# Sheet3.net
KiCad netlist of a schematic drawn in Altium Designer
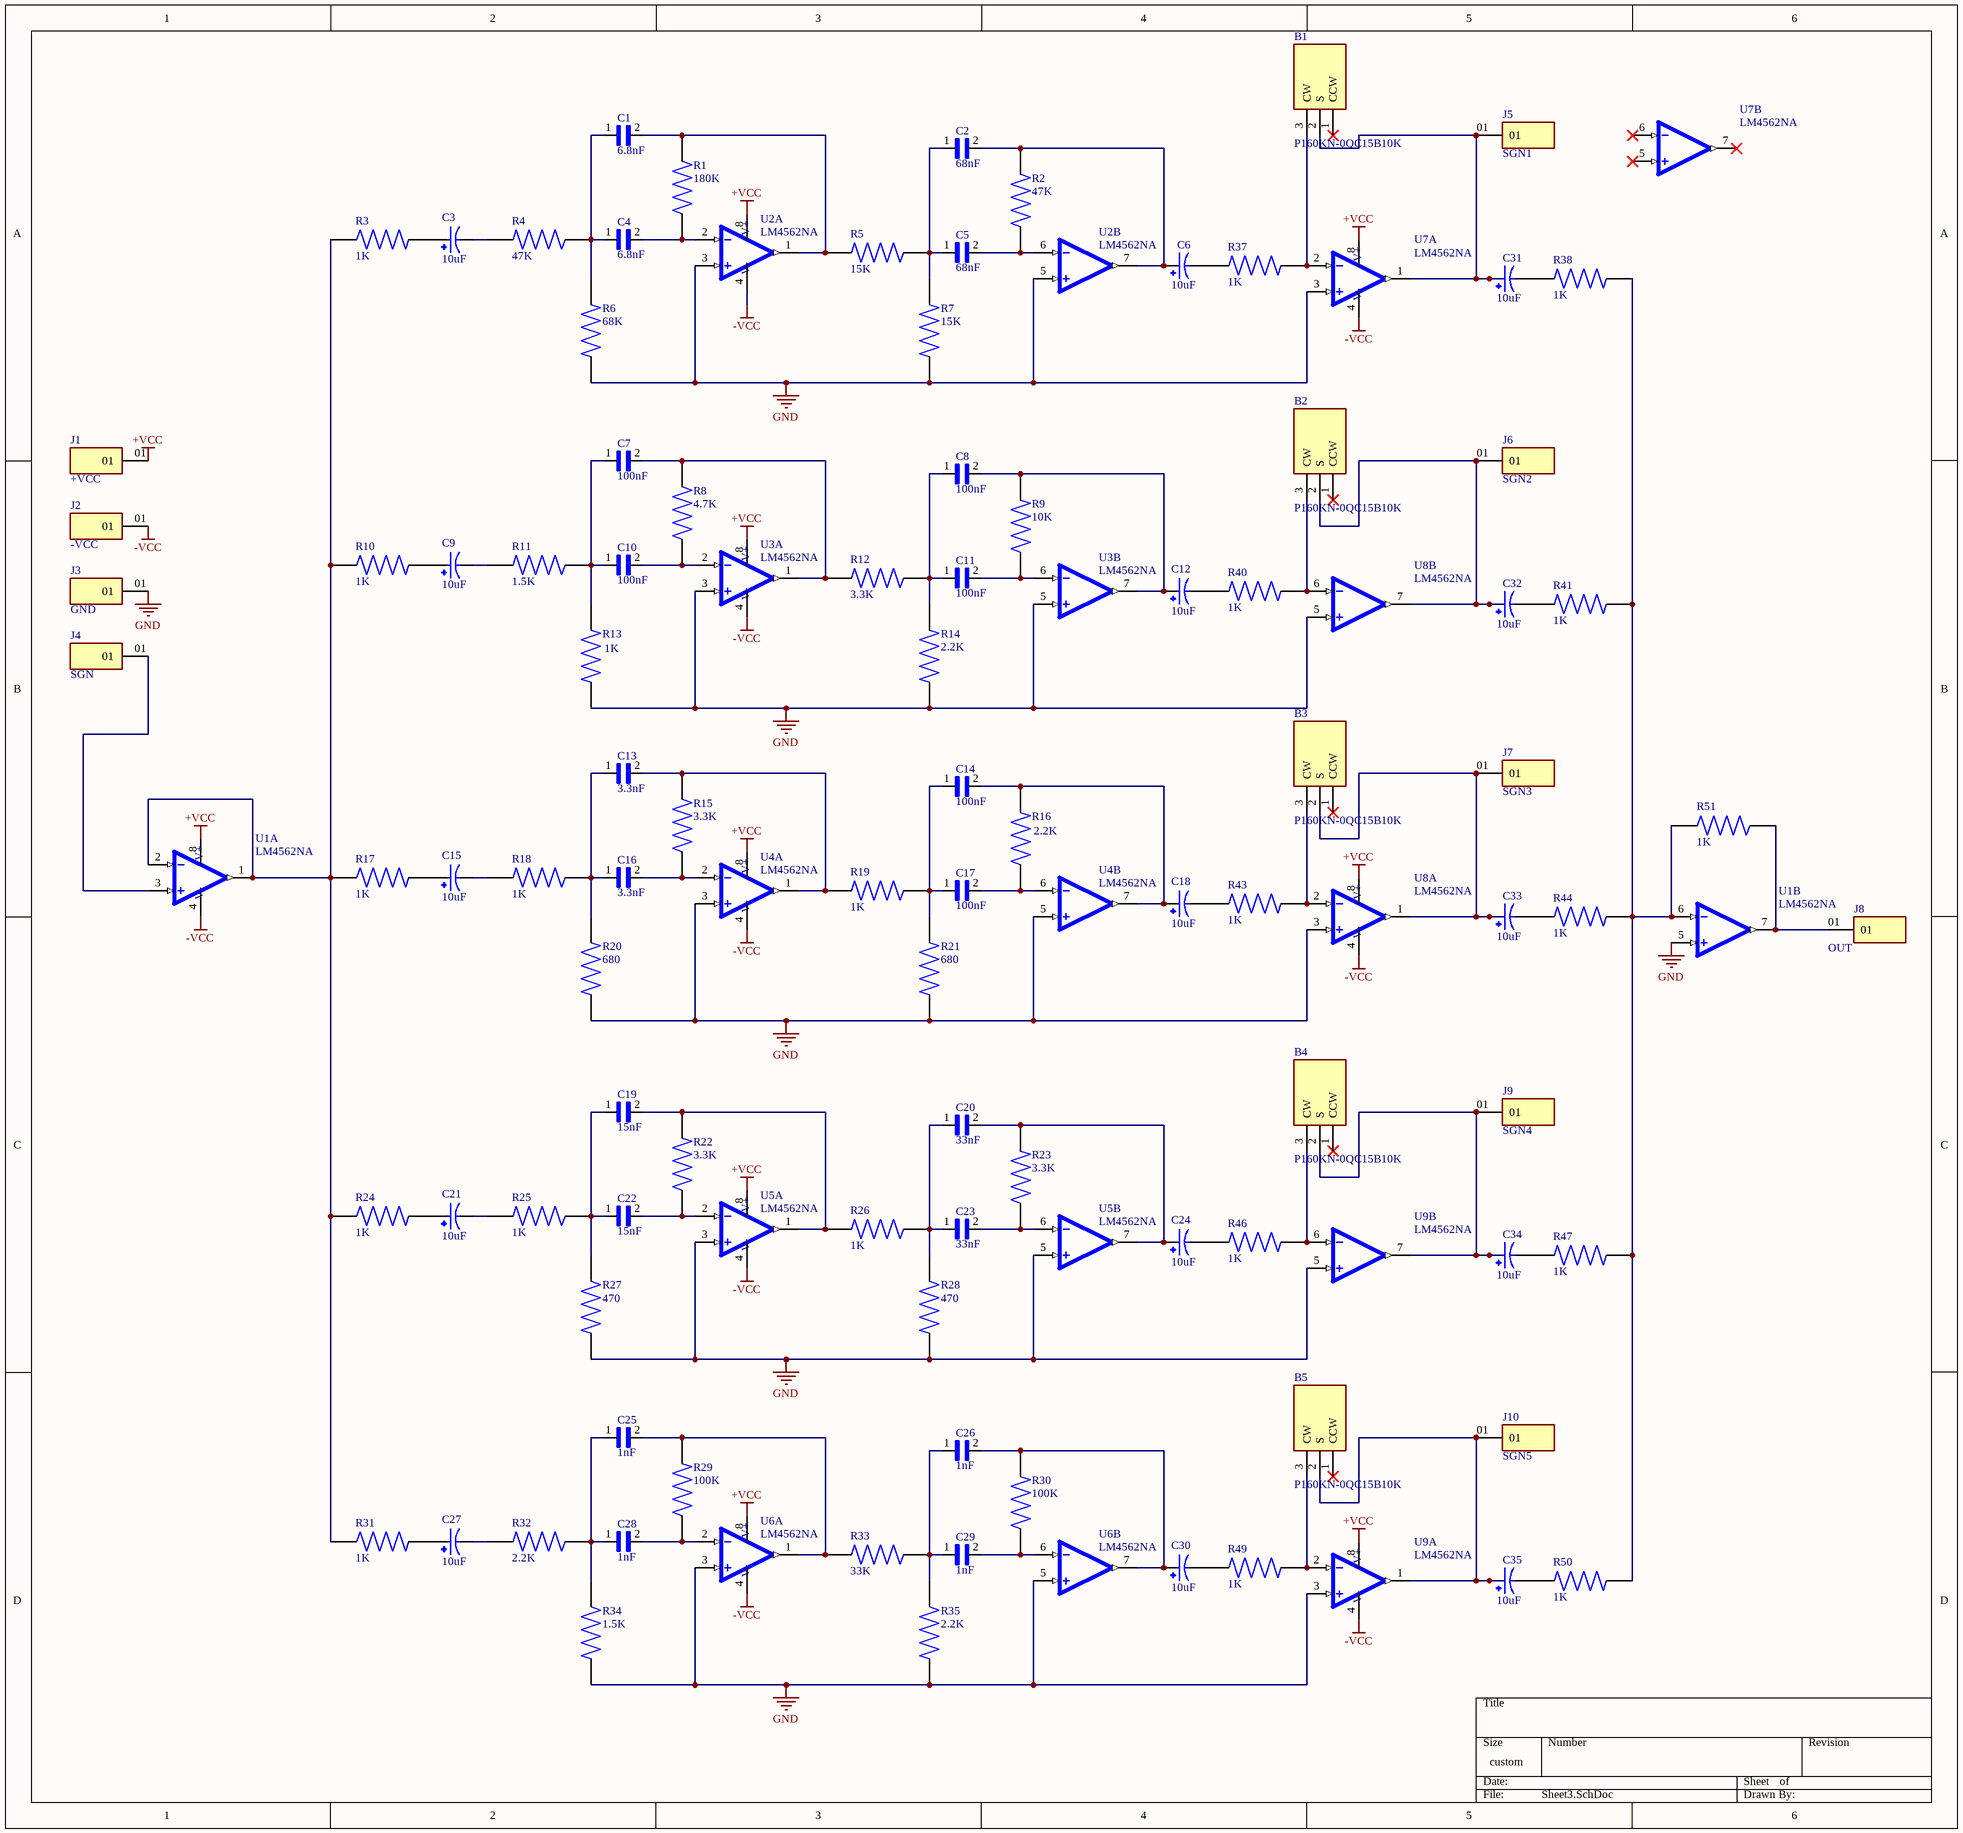
[diagram p0: Sheet3.SchDoc]

(export (version "E")
  (design (tool "Eeschema 10.0.6"))
  (components
    (comp (ref "B1")
      (value "P160KN-0QC15B10K")
      (footprint "P160KN0QC15B10K")
      (description "Potentiometers 16mm Rotary Panel Potentiometer")
      (fields (field (name "MOUSER PART NUMBER") "858-P160KN-0QC15B10K"))
      (libsource (lib "Copy of P160KN-0QC15B10K") (part "P160KN-0QC15B10K"))
    )
    (comp (ref "B2")
      (value "P160KN-0QC15B10K")
      (footprint "P160KN0QC15B10K")
      (description "Potentiometers 16mm Rotary Panel Potentiometer")
      (fields (field (name "MOUSER PART NUMBER") "858-P160KN-0QC15B10K"))
      (libsource (lib "Copy of P160KN-0QC15B10K") (part "P160KN-0QC15B10K"))
    )
    (comp (ref "B3")
      (value "P160KN-0QC15B10K")
      (footprint "P160KN0QC15B10K")
      (description "Potentiometers 16mm Rotary Panel Potentiometer")
      (fields (field (name "MOUSER PART NUMBER") "858-P160KN-0QC15B10K"))
      (libsource (lib "Copy of P160KN-0QC15B10K") (part "P160KN-0QC15B10K"))
    )
    (comp (ref "B4")
      (value "P160KN-0QC15B10K")
      (footprint "P160KN0QC15B10K")
      (description "Potentiometers 16mm Rotary Panel Potentiometer")
      (fields (field (name "MOUSER PART NUMBER") "858-P160KN-0QC15B10K"))
      (libsource (lib "Copy of P160KN-0QC15B10K") (part "P160KN-0QC15B10K"))
    )
    (comp (ref "B5")
      (value "P160KN-0QC15B10K")
      (footprint "P160KN0QC15B10K")
      (description "Potentiometers 16mm Rotary Panel Potentiometer")
      (fields (field (name "MOUSER PART NUMBER") "858-P160KN-0QC15B10K"))
      (libsource (lib "Copy of P160KN-0QC15B10K") (part "P160KN-0QC15B10K"))
    )
    (comp (ref "C1")
      (value "6.8nF")
      (footprint "CAPRB500W50L550T350H600")
      (description "0.1ÂµF Â±10% 250V Ceramic Capacitor X7R Radial")
      (fields (field (name "MF") "TDK") (field (name "MP") "FG26X7R2E104KNT06"))
      (libsource (lib "FG26X7R2E104KNT06") (part "FG26X7R2E104KNT06"))
    )
    (comp (ref "C2")
      (value "68nF")
      (footprint "CAPRB500W50L550T350H600")
      (description "0.1ÂµF Â±10% 250V Ceramic Capacitor X7R Radial")
      (fields (field (name "MF") "TDK") (field (name "MP") "FG26X7R2E104KNT06"))
      (libsource (lib "FG26X7R2E104KNT06") (part "FG26X7R2E104KNT06"))
    )
    (comp (ref "C3")
      (value "10uF")
      (footprint "CAPPRD500W60D1250H2000:CAPPRD500W60D1250H2000")
      (description "CAP ALUM 10UF 20% 450V RADIAL")
      (fields (field (name "MP") "ECA-2WM100B") (field (name "MF") "Panasonic"))
      (libsource (lib "ECA2WM100B") (part "ECA2WM100B"))
    )
    (comp (ref "C4")
      (value "6.8nF")
      (footprint "CAPRB500W50L550T350H600")
      (description "0.1ÂµF Â±10% 250V Ceramic Capacitor X7R Radial")
      (fields (field (name "MF") "TDK") (field (name "MP") "FG26X7R2E104KNT06"))
      (libsource (lib "FG26X7R2E104KNT06") (part "FG26X7R2E104KNT06"))
    )
    (comp (ref "C5")
      (value "68nF")
      (footprint "CAPRB500W50L550T350H600")
      (description "0.1ÂµF Â±10% 250V Ceramic Capacitor X7R Radial")
      (fields (field (name "MF") "TDK") (field (name "MP") "FG26X7R2E104KNT06"))
      (libsource (lib "FG26X7R2E104KNT06") (part "FG26X7R2E104KNT06"))
    )
    (comp (ref "C6")
      (value "10uF")
      (footprint "CAPPRD500W60D1250H2000:CAPPRD500W60D1250H2000")
      (description "CAP ALUM 10UF 20% 450V RADIAL")
      (fields (field (name "MP") "ECA-2WM100B") (field (name "MF") "Panasonic"))
      (libsource (lib "ECA2WM100B") (part "ECA2WM100B"))
    )
    (comp (ref "C7")
      (value "100nF")
      (footprint "CAPRB500W50L550T350H600")
      (description "0.1ÂµF Â±10% 250V Ceramic Capacitor X7R Radial")
      (fields (field (name "MF") "TDK") (field (name "MP") "FG26X7R2E104KNT06"))
      (libsource (lib "FG26X7R2E104KNT06") (part "FG26X7R2E104KNT06"))
    )
    (comp (ref "C8")
      (value "100nF")
      (footprint "CAPRB500W50L550T350H600")
      (description "0.1ÂµF Â±10% 250V Ceramic Capacitor X7R Radial")
      (fields (field (name "MF") "TDK") (field (name "MP") "FG26X7R2E104KNT06"))
      (libsource (lib "FG26X7R2E104KNT06") (part "FG26X7R2E104KNT06"))
    )
    (comp (ref "C9")
      (value "10uF")
      (footprint "CAPPRD500W60D1250H2000:CAPPRD500W60D1250H2000")
      (description "CAP ALUM 10UF 20% 450V RADIAL")
      (fields (field (name "MP") "ECA-2WM100B") (field (name "MF") "Panasonic"))
      (libsource (lib "ECA2WM100B") (part "ECA2WM100B"))
    )
    (comp (ref "C10")
      (value "100nF")
      (footprint "CAPRB500W50L550T350H600")
      (description "0.1ÂµF Â±10% 250V Ceramic Capacitor X7R Radial")
      (fields (field (name "MF") "TDK") (field (name "MP") "FG26X7R2E104KNT06"))
      (libsource (lib "FG26X7R2E104KNT06") (part "FG26X7R2E104KNT06"))
    )
    (comp (ref "C11")
      (value "100nF")
      (footprint "CAPRB500W50L550T350H600")
      (description "0.1ÂµF Â±10% 250V Ceramic Capacitor X7R Radial")
      (fields (field (name "MF") "TDK") (field (name "MP") "FG26X7R2E104KNT06"))
      (libsource (lib "FG26X7R2E104KNT06") (part "FG26X7R2E104KNT06"))
    )
    (comp (ref "C12")
      (value "10uF")
      (footprint "CAPPRD500W60D1250H2000:CAPPRD500W60D1250H2000")
      (description "CAP ALUM 10UF 20% 450V RADIAL")
      (fields (field (name "MP") "ECA-2WM100B") (field (name "MF") "Panasonic"))
      (libsource (lib "ECA2WM100B") (part "ECA2WM100B"))
    )
    (comp (ref "C13")
      (value "3.3nF")
      (footprint "CAPRB500W50L550T350H600")
      (description "0.1ÂµF Â±10% 250V Ceramic Capacitor X7R Radial")
      (fields (field (name "MF") "TDK") (field (name "MP") "FG26X7R2E104KNT06"))
      (libsource (lib "FG26X7R2E104KNT06") (part "FG26X7R2E104KNT06"))
    )
    (comp (ref "C14")
      (value "100nF")
      (footprint "CAPRB500W50L550T350H600")
      (description "0.1ÂµF Â±10% 250V Ceramic Capacitor X7R Radial")
      (fields (field (name "MF") "TDK") (field (name "MP") "FG26X7R2E104KNT06"))
      (libsource (lib "FG26X7R2E104KNT06") (part "FG26X7R2E104KNT06"))
    )
    (comp (ref "C15")
      (value "10uF")
      (footprint "CAPPRD500W60D1250H2000:CAPPRD500W60D1250H2000")
      (description "CAP ALUM 10UF 20% 450V RADIAL")
      (fields (field (name "MP") "ECA-2WM100B") (field (name "MF") "Panasonic"))
      (libsource (lib "ECA2WM100B") (part "ECA2WM100B"))
    )
    (comp (ref "C16")
      (value "3.3nF")
      (footprint "CAPRB500W50L550T350H600")
      (description "0.1ÂµF Â±10% 250V Ceramic Capacitor X7R Radial")
      (fields (field (name "MF") "TDK") (field (name "MP") "FG26X7R2E104KNT06"))
      (libsource (lib "FG26X7R2E104KNT06") (part "FG26X7R2E104KNT06"))
    )
    (comp (ref "C17")
      (value "100nF")
      (footprint "CAPRB500W50L550T350H600")
      (description "0.1ÂµF Â±10% 250V Ceramic Capacitor X7R Radial")
      (fields (field (name "MF") "TDK") (field (name "MP") "FG26X7R2E104KNT06"))
      (libsource (lib "FG26X7R2E104KNT06") (part "FG26X7R2E104KNT06"))
    )
    (comp (ref "C18")
      (value "10uF")
      (footprint "CAPPRD500W60D1250H2000:CAPPRD500W60D1250H2000")
      (description "CAP ALUM 10UF 20% 450V RADIAL")
      (fields (field (name "MP") "ECA-2WM100B") (field (name "MF") "Panasonic"))
      (libsource (lib "ECA2WM100B") (part "ECA2WM100B"))
    )
    (comp (ref "C19")
      (value "15nF")
      (footprint "CAPRB500W50L550T350H600")
      (description "0.1ÂµF Â±10% 250V Ceramic Capacitor X7R Radial")
      (fields (field (name "MF") "TDK") (field (name "MP") "FG26X7R2E104KNT06"))
      (libsource (lib "FG26X7R2E104KNT06") (part "FG26X7R2E104KNT06"))
    )
    (comp (ref "C20")
      (value "33nF")
      (footprint "CAPRB500W50L550T350H600")
      (description "0.1ÂµF Â±10% 250V Ceramic Capacitor X7R Radial")
      (fields (field (name "MF") "TDK") (field (name "MP") "FG26X7R2E104KNT06"))
      (libsource (lib "FG26X7R2E104KNT06") (part "FG26X7R2E104KNT06"))
    )
    (comp (ref "C21")
      (value "10uF")
      (footprint "CAPPRD500W60D1250H2000:CAPPRD500W60D1250H2000")
      (description "CAP ALUM 10UF 20% 450V RADIAL")
      (fields (field (name "MP") "ECA-2WM100B") (field (name "MF") "Panasonic"))
      (libsource (lib "ECA2WM100B") (part "ECA2WM100B"))
    )
    (comp (ref "C22")
      (value "15nF")
      (footprint "CAPRB500W50L550T350H600")
      (description "0.1ÂµF Â±10% 250V Ceramic Capacitor X7R Radial")
      (fields (field (name "MF") "TDK") (field (name "MP") "FG26X7R2E104KNT06"))
      (libsource (lib "FG26X7R2E104KNT06") (part "FG26X7R2E104KNT06"))
    )
    (comp (ref "C23")
      (value "33nF")
      (footprint "CAPRB500W50L550T350H600")
      (description "0.1ÂµF Â±10% 250V Ceramic Capacitor X7R Radial")
      (fields (field (name "MF") "TDK") (field (name "MP") "FG26X7R2E104KNT06"))
      (libsource (lib "FG26X7R2E104KNT06") (part "FG26X7R2E104KNT06"))
    )
    (comp (ref "C24")
      (value "10uF")
      (footprint "CAPPRD500W60D1250H2000:CAPPRD500W60D1250H2000")
      (description "CAP ALUM 10UF 20% 450V RADIAL")
      (fields (field (name "MP") "ECA-2WM100B") (field (name "MF") "Panasonic"))
      (libsource (lib "ECA2WM100B") (part "ECA2WM100B"))
    )
    (comp (ref "C25")
      (value "1nF")
      (footprint "CAPRB500W50L550T350H600")
      (description "0.1ÂµF Â±10% 250V Ceramic Capacitor X7R Radial")
      (fields (field (name "MF") "TDK") (field (name "MP") "FG26X7R2E104KNT06"))
      (libsource (lib "FG26X7R2E104KNT06") (part "FG26X7R2E104KNT06"))
    )
    (comp (ref "C26")
      (value "1nF")
      (footprint "CAPRB500W50L550T350H600")
      (description "0.1ÂµF Â±10% 250V Ceramic Capacitor X7R Radial")
      (fields (field (name "MF") "TDK") (field (name "MP") "FG26X7R2E104KNT06"))
      (libsource (lib "FG26X7R2E104KNT06") (part "FG26X7R2E104KNT06"))
    )
    (comp (ref "C27")
      (value "10uF")
      (footprint "CAPPRD500W60D1250H2000:CAPPRD500W60D1250H2000")
      (description "CAP ALUM 10UF 20% 450V RADIAL")
      (fields (field (name "MP") "ECA-2WM100B") (field (name "MF") "Panasonic"))
      (libsource (lib "ECA2WM100B") (part "ECA2WM100B"))
    )
    (comp (ref "C28")
      (value "1nF")
      (footprint "CAPRB500W50L550T350H600")
      (description "0.1ÂµF Â±10% 250V Ceramic Capacitor X7R Radial")
      (fields (field (name "MF") "TDK") (field (name "MP") "FG26X7R2E104KNT06"))
      (libsource (lib "FG26X7R2E104KNT06") (part "FG26X7R2E104KNT06"))
    )
    (comp (ref "C29")
      (value "1nF")
      (footprint "CAPRB500W50L550T350H600")
      (description "0.1ÂµF Â±10% 250V Ceramic Capacitor X7R Radial")
      (fields (field (name "MF") "TDK") (field (name "MP") "FG26X7R2E104KNT06"))
      (libsource (lib "FG26X7R2E104KNT06") (part "FG26X7R2E104KNT06"))
    )
    (comp (ref "C30")
      (value "10uF")
      (footprint "CAPPRD500W60D1250H2000:CAPPRD500W60D1250H2000")
      (description "CAP ALUM 10UF 20% 450V RADIAL")
      (fields (field (name "MP") "ECA-2WM100B") (field (name "MF") "Panasonic"))
      (libsource (lib "ECA2WM100B") (part "ECA2WM100B"))
    )
    (comp (ref "C31")
      (value "10uF")
      (footprint "CAPPRD500W60D1250H2000:CAPPRD500W60D1250H2000")
      (description "CAP ALUM 10UF 20% 450V RADIAL")
      (fields (field (name "MP") "ECA-2WM100B") (field (name "MF") "Panasonic"))
      (libsource (lib "ECA2WM100B") (part "ECA2WM100B"))
    )
    (comp (ref "C32")
      (value "10uF")
      (footprint "CAPPRD500W60D1250H2000:CAPPRD500W60D1250H2000")
      (description "CAP ALUM 10UF 20% 450V RADIAL")
      (fields (field (name "MP") "ECA-2WM100B") (field (name "MF") "Panasonic"))
      (libsource (lib "ECA2WM100B") (part "ECA2WM100B"))
    )
    (comp (ref "C33")
      (value "10uF")
      (footprint "CAPPRD500W60D1250H2000:CAPPRD500W60D1250H2000")
      (description "CAP ALUM 10UF 20% 450V RADIAL")
      (fields (field (name "MP") "ECA-2WM100B") (field (name "MF") "Panasonic"))
      (libsource (lib "ECA2WM100B") (part "ECA2WM100B"))
    )
    (comp (ref "C34")
      (value "10uF")
      (footprint "CAPPRD500W60D1250H2000:CAPPRD500W60D1250H2000")
      (description "CAP ALUM 10UF 20% 450V RADIAL")
      (fields (field (name "MP") "ECA-2WM100B") (field (name "MF") "Panasonic"))
      (libsource (lib "ECA2WM100B") (part "ECA2WM100B"))
    )
    (comp (ref "C35")
      (value "10uF")
      (footprint "CAPPRD500W60D1250H2000:CAPPRD500W60D1250H2000")
      (description "CAP ALUM 10UF 20% 450V RADIAL")
      (fields (field (name "MP") "ECA-2WM100B") (field (name "MF") "Panasonic"))
      (libsource (lib "ECA2WM100B") (part "ECA2WM100B"))
    )
    (comp (ref "J1")
      (value "+VCC")
      (footprint "SAMTEC_MTMM-101-XX-X-S-XXX:SAMTEC_MTMM-101-XX-X-S-XXX")
      (description "Connector Header position")
      (fields (field (name "MP") "MTMM-101-XX-X-S-XXX"))
      (libsource (lib "") (part "MTMM-101-XX-X-S-XXX_1"))
    )
    (comp (ref "J2")
      (value "-VCC")
      (footprint "SAMTEC_MTMM-101-XX-X-S-XXX:SAMTEC_MTMM-101-XX-X-S-XXX")
      (description "Connector Header position")
      (fields (field (name "MP") "MTMM-101-XX-X-S-XXX"))
      (libsource (lib "") (part "MTMM-101-XX-X-S-XXX_1"))
    )
    (comp (ref "J3")
      (value "GND")
      (footprint "SAMTEC_MTMM-101-XX-X-S-XXX:SAMTEC_MTMM-101-XX-X-S-XXX")
      (description "Connector Header position")
      (fields (field (name "MP") "MTMM-101-XX-X-S-XXX"))
      (libsource (lib "") (part "MTMM-101-XX-X-S-XXX_1"))
    )
    (comp (ref "J4")
      (value "SGN")
      (footprint "SAMTEC_MTMM-101-XX-X-S-XXX:SAMTEC_MTMM-101-XX-X-S-XXX")
      (description "Connector Header position")
      (fields (field (name "MP") "MTMM-101-XX-X-S-XXX"))
      (libsource (lib "") (part "MTMM-101-XX-X-S-XXX_1"))
    )
    (comp (ref "J5")
      (value "SGN1")
      (footprint "SAMTEC_MTMM-101-XX-X-S-XXX:SAMTEC_MTMM-101-XX-X-S-XXX")
      (description "Connector Header position")
      (fields (field (name "MP") "MTMM-101-XX-X-S-XXX"))
      (libsource (lib "MTMM-101-XX-X-S-XXX") (part "MTMM-101-XX-X-S-XXX"))
    )
    (comp (ref "J6")
      (value "SGN2")
      (footprint "SAMTEC_MTMM-101-XX-X-S-XXX:SAMTEC_MTMM-101-XX-X-S-XXX")
      (description "Connector Header position")
      (fields (field (name "MP") "MTMM-101-XX-X-S-XXX"))
      (libsource (lib "MTMM-101-XX-X-S-XXX") (part "MTMM-101-XX-X-S-XXX"))
    )
    (comp (ref "J7")
      (value "SGN3")
      (footprint "SAMTEC_MTMM-101-XX-X-S-XXX:SAMTEC_MTMM-101-XX-X-S-XXX")
      (description "Connector Header position")
      (fields (field (name "MP") "MTMM-101-XX-X-S-XXX"))
      (libsource (lib "MTMM-101-XX-X-S-XXX") (part "MTMM-101-XX-X-S-XXX"))
    )
    (comp (ref "J8")
      (value "OUT")
      (footprint "SAMTEC_MTMM-101-XX-X-S-XXX:SAMTEC_MTMM-101-XX-X-S-XXX")
      (description "Connector Header position")
      (fields (field (name "MP") "MTMM-101-XX-X-S-XXX"))
      (libsource (lib "MTMM-101-XX-X-S-XXX") (part "MTMM-101-XX-X-S-XXX"))
    )
    (comp (ref "J9")
      (value "SGN4")
      (footprint "SAMTEC_MTMM-101-XX-X-S-XXX:SAMTEC_MTMM-101-XX-X-S-XXX")
      (description "Connector Header position")
      (fields (field (name "MP") "MTMM-101-XX-X-S-XXX"))
      (libsource (lib "MTMM-101-XX-X-S-XXX") (part "MTMM-101-XX-X-S-XXX"))
    )
    (comp (ref "J10")
      (value "SGN5")
      (footprint "SAMTEC_MTMM-101-XX-X-S-XXX:SAMTEC_MTMM-101-XX-X-S-XXX")
      (description "Connector Header position")
      (fields (field (name "MP") "MTMM-101-XX-X-S-XXX"))
      (libsource (lib "MTMM-101-XX-X-S-XXX") (part "MTMM-101-XX-X-S-XXX"))
    )
    (comp (ref "R1")
      (value "180K")
      (footprint "RESAD1100W55L680D260")
      (description "1.78 kOhms Â±1% 0.25W, 1/4W Through Hole Resistor Axial - Metal Film")
      (fields (field (name "MF") "Yageo") (field (name "MP") "MFR-25FBF52-1K"))
      (libsource (lib "MFR-25FBF52-1K") (part "MFR-25FBF52-1K"))
    )
    (comp (ref "R2")
      (value "47K")
      (footprint "RESAD1100W55L680D260")
      (description "1.78 kOhms Â±1% 0.25W, 1/4W Through Hole Resistor Axial - Metal Film")
      (fields (field (name "MF") "Yageo") (field (name "MP") "MFR-25FBF52-1K"))
      (libsource (lib "MFR-25FBF52-1K") (part "MFR-25FBF52-1K"))
    )
    (comp (ref "R3")
      (value "1K")
      (footprint "RESAD1100W55L680D260")
      (description "1.78 kOhms Â±1% 0.25W, 1/4W Through Hole Resistor Axial - Metal Film")
      (fields (field (name "MF") "Yageo") (field (name "MP") "MFR-25FBF52-1K"))
      (libsource (lib "MFR-25FBF52-1K") (part "MFR-25FBF52-1K"))
    )
    (comp (ref "R4")
      (value "47K")
      (footprint "RESAD1100W55L680D260")
      (description "1.78 kOhms Â±1% 0.25W, 1/4W Through Hole Resistor Axial - Metal Film")
      (fields (field (name "MF") "Yageo") (field (name "MP") "MFR-25FBF52-1K"))
      (libsource (lib "MFR-25FBF52-1K") (part "MFR-25FBF52-1K"))
    )
    (comp (ref "R5")
      (value "15K")
      (footprint "RESAD1100W55L680D260")
      (description "1.78 kOhms Â±1% 0.25W, 1/4W Through Hole Resistor Axial - Metal Film")
      (fields (field (name "MF") "Yageo") (field (name "MP") "MFR-25FBF52-1K"))
      (libsource (lib "MFR-25FBF52-1K") (part "MFR-25FBF52-1K"))
    )
    (comp (ref "R6")
      (value "68K")
      (footprint "RESAD1100W55L680D260")
      (description "1.78 kOhms Â±1% 0.25W, 1/4W Through Hole Resistor Axial - Metal Film")
      (fields (field (name "MF") "Yageo") (field (name "MP") "MFR-25FBF52-1K"))
      (libsource (lib "MFR-25FBF52-1K") (part "MFR-25FBF52-1K"))
    )
    (comp (ref "R7")
      (value "15K")
      (footprint "RESAD1100W55L680D260")
      (description "1.78 kOhms Â±1% 0.25W, 1/4W Through Hole Resistor Axial - Metal Film")
      (fields (field (name "MF") "Yageo") (field (name "MP") "MFR-25FBF52-1K"))
      (libsource (lib "MFR-25FBF52-1K") (part "MFR-25FBF52-1K"))
    )
    (comp (ref "R8")
      (value "4.7K")
      (footprint "RESAD1100W55L680D260")
      (description "1.78 kOhms Â±1% 0.25W, 1/4W Through Hole Resistor Axial - Metal Film")
      (fields (field (name "MF") "Yageo") (field (name "MP") "MFR-25FBF52-1K"))
      (libsource (lib "MFR-25FBF52-1K") (part "MFR-25FBF52-1K"))
    )
    (comp (ref "R9")
      (value "10K")
      (footprint "RESAD1100W55L680D260")
      (description "1.78 kOhms Â±1% 0.25W, 1/4W Through Hole Resistor Axial - Metal Film")
      (fields (field (name "MF") "Yageo") (field (name "MP") "MFR-25FBF52-1K"))
      (libsource (lib "MFR-25FBF52-1K") (part "MFR-25FBF52-1K"))
    )
    (comp (ref "R10")
      (value "1K")
      (footprint "RESAD1100W55L680D260")
      (description "1.78 kOhms Â±1% 0.25W, 1/4W Through Hole Resistor Axial - Metal Film")
      (fields (field (name "MF") "Yageo") (field (name "MP") "MFR-25FBF52-1K"))
      (libsource (lib "MFR-25FBF52-1K") (part "MFR-25FBF52-1K"))
    )
    (comp (ref "R11")
      (value "1.5K")
      (footprint "RESAD1100W55L680D260")
      (description "1.78 kOhms Â±1% 0.25W, 1/4W Through Hole Resistor Axial - Metal Film")
      (fields (field (name "MF") "Yageo") (field (name "MP") "MFR-25FBF52-1K"))
      (libsource (lib "MFR-25FBF52-1K") (part "MFR-25FBF52-1K"))
    )
    (comp (ref "R12")
      (value "3.3K")
      (footprint "RESAD1100W55L680D260")
      (description "1.78 kOhms Â±1% 0.25W, 1/4W Through Hole Resistor Axial - Metal Film")
      (fields (field (name "MF") "Yageo") (field (name "MP") "MFR-25FBF52-1K"))
      (libsource (lib "MFR-25FBF52-1K") (part "MFR-25FBF52-1K"))
    )
    (comp (ref "R13")
      (value "1K")
      (footprint "RESAD1100W55L680D260")
      (description "1.78 kOhms Â±1% 0.25W, 1/4W Through Hole Resistor Axial - Metal Film")
      (fields (field (name "MF") "Yageo") (field (name "MP") "MFR-25FBF52-1K"))
      (libsource (lib "MFR-25FBF52-1K") (part "MFR-25FBF52-1K"))
    )
    (comp (ref "R14")
      (value "2.2K")
      (footprint "RESAD1100W55L680D260")
      (description "1.78 kOhms Â±1% 0.25W, 1/4W Through Hole Resistor Axial - Metal Film")
      (fields (field (name "MF") "Yageo") (field (name "MP") "MFR-25FBF52-1K"))
      (libsource (lib "MFR-25FBF52-1K") (part "MFR-25FBF52-1K"))
    )
    (comp (ref "R15")
      (value "3.3K")
      (footprint "RESAD1100W55L680D260")
      (description "1.78 kOhms Â±1% 0.25W, 1/4W Through Hole Resistor Axial - Metal Film")
      (fields (field (name "MF") "Yageo") (field (name "MP") "MFR-25FBF52-1K"))
      (libsource (lib "MFR-25FBF52-1K") (part "MFR-25FBF52-1K"))
    )
    (comp (ref "R16")
      (value "2.2K")
      (footprint "RESAD1100W55L680D260")
      (description "1.78 kOhms Â±1% 0.25W, 1/4W Through Hole Resistor Axial - Metal Film")
      (fields (field (name "MF") "Yageo") (field (name "MP") "MFR-25FBF52-1K"))
      (libsource (lib "MFR-25FBF52-1K") (part "MFR-25FBF52-1K"))
    )
    (comp (ref "R17")
      (value "1K")
      (footprint "RESAD1100W55L680D260")
      (description "1.78 kOhms Â±1% 0.25W, 1/4W Through Hole Resistor Axial - Metal Film")
      (fields (field (name "MF") "Yageo") (field (name "MP") "MFR-25FBF52-1K"))
      (libsource (lib "MFR-25FBF52-1K") (part "MFR-25FBF52-1K"))
    )
    (comp (ref "R18")
      (value "1K")
      (footprint "RESAD1100W55L680D260")
      (description "1.78 kOhms Â±1% 0.25W, 1/4W Through Hole Resistor Axial - Metal Film")
      (fields (field (name "MF") "Yageo") (field (name "MP") "MFR-25FBF52-1K"))
      (libsource (lib "MFR-25FBF52-1K") (part "MFR-25FBF52-1K"))
    )
    (comp (ref "R19")
      (value "1K")
      (footprint "RESAD1100W55L680D260")
      (description "1.78 kOhms Â±1% 0.25W, 1/4W Through Hole Resistor Axial - Metal Film")
      (fields (field (name "MF") "Yageo") (field (name "MP") "MFR-25FBF52-1K"))
      (libsource (lib "MFR-25FBF52-1K") (part "MFR-25FBF52-1K"))
    )
    (comp (ref "R20")
      (value "680")
      (footprint "RESAD1100W55L680D260")
      (description "1.78 kOhms Â±1% 0.25W, 1/4W Through Hole Resistor Axial - Metal Film")
      (fields (field (name "MF") "Yageo") (field (name "MP") "MFR-25FBF52-1K"))
      (libsource (lib "MFR-25FBF52-1K") (part "MFR-25FBF52-1K"))
    )
    (comp (ref "R21")
      (value "680")
      (footprint "RESAD1100W55L680D260")
      (description "1.78 kOhms Â±1% 0.25W, 1/4W Through Hole Resistor Axial - Metal Film")
      (fields (field (name "MF") "Yageo") (field (name "MP") "MFR-25FBF52-1K"))
      (libsource (lib "MFR-25FBF52-1K") (part "MFR-25FBF52-1K"))
    )
    (comp (ref "R22")
      (value "3.3K")
      (footprint "RESAD1100W55L680D260")
      (description "1.78 kOhms Â±1% 0.25W, 1/4W Through Hole Resistor Axial - Metal Film")
      (fields (field (name "MF") "Yageo") (field (name "MP") "MFR-25FBF52-1K"))
      (libsource (lib "MFR-25FBF52-1K") (part "MFR-25FBF52-1K"))
    )
    (comp (ref "R23")
      (value "3.3K")
      (footprint "RESAD1100W55L680D260")
      (description "1.78 kOhms Â±1% 0.25W, 1/4W Through Hole Resistor Axial - Metal Film")
      (fields (field (name "MF") "Yageo") (field (name "MP") "MFR-25FBF52-1K"))
      (libsource (lib "MFR-25FBF52-1K") (part "MFR-25FBF52-1K"))
    )
    (comp (ref "R24")
      (value "1K")
      (footprint "RESAD1100W55L680D260")
      (description "1.78 kOhms Â±1% 0.25W, 1/4W Through Hole Resistor Axial - Metal Film")
      (fields (field (name "MF") "Yageo") (field (name "MP") "MFR-25FBF52-1K"))
      (libsource (lib "MFR-25FBF52-1K") (part "MFR-25FBF52-1K"))
    )
    (comp (ref "R25")
      (value "1K")
      (footprint "RESAD1100W55L680D260")
      (description "1.78 kOhms Â±1% 0.25W, 1/4W Through Hole Resistor Axial - Metal Film")
      (fields (field (name "MF") "Yageo") (field (name "MP") "MFR-25FBF52-1K"))
      (libsource (lib "MFR-25FBF52-1K") (part "MFR-25FBF52-1K"))
    )
    (comp (ref "R26")
      (value "1K")
      (footprint "RESAD1100W55L680D260")
      (description "1.78 kOhms Â±1% 0.25W, 1/4W Through Hole Resistor Axial - Metal Film")
      (fields (field (name "MF") "Yageo") (field (name "MP") "MFR-25FBF52-1K"))
      (libsource (lib "MFR-25FBF52-1K") (part "MFR-25FBF52-1K"))
    )
    (comp (ref "R27")
      (value "470")
      (footprint "RESAD1100W55L680D260")
      (description "1.78 kOhms Â±1% 0.25W, 1/4W Through Hole Resistor Axial - Metal Film")
      (fields (field (name "MF") "Yageo") (field (name "MP") "MFR-25FBF52-1K"))
      (libsource (lib "MFR-25FBF52-1K") (part "MFR-25FBF52-1K"))
    )
    (comp (ref "R28")
      (value "470")
      (footprint "RESAD1100W55L680D260")
      (description "1.78 kOhms Â±1% 0.25W, 1/4W Through Hole Resistor Axial - Metal Film")
      (fields (field (name "MF") "Yageo") (field (name "MP") "MFR-25FBF52-1K"))
      (libsource (lib "MFR-25FBF52-1K") (part "MFR-25FBF52-1K"))
    )
    (comp (ref "R29")
      (value "100K")
      (footprint "RESAD1100W55L680D260")
      (description "1.78 kOhms Â±1% 0.25W, 1/4W Through Hole Resistor Axial - Metal Film")
      (fields (field (name "MF") "Yageo") (field (name "MP") "MFR-25FBF52-1K"))
      (libsource (lib "MFR-25FBF52-1K") (part "MFR-25FBF52-1K"))
    )
    (comp (ref "R30")
      (value "100K")
      (footprint "RESAD1100W55L680D260")
      (description "1.78 kOhms Â±1% 0.25W, 1/4W Through Hole Resistor Axial - Metal Film")
      (fields (field (name "MF") "Yageo") (field (name "MP") "MFR-25FBF52-1K"))
      (libsource (lib "MFR-25FBF52-1K") (part "MFR-25FBF52-1K"))
    )
    (comp (ref "R31")
      (value "1K")
      (footprint "RESAD1100W55L680D260")
      (description "1.78 kOhms Â±1% 0.25W, 1/4W Through Hole Resistor Axial - Metal Film")
      (fields (field (name "MF") "Yageo") (field (name "MP") "MFR-25FBF52-1K"))
      (libsource (lib "MFR-25FBF52-1K") (part "MFR-25FBF52-1K"))
    )
    (comp (ref "R32")
      (value "2.2K")
      (footprint "RESAD1100W55L680D260")
      (description "1.78 kOhms Â±1% 0.25W, 1/4W Through Hole Resistor Axial - Metal Film")
      (fields (field (name "MF") "Yageo") (field (name "MP") "MFR-25FBF52-1K"))
      (libsource (lib "MFR-25FBF52-1K") (part "MFR-25FBF52-1K"))
    )
    (comp (ref "R33")
      (value "33K")
      (footprint "RESAD1100W55L680D260")
      (description "1.78 kOhms Â±1% 0.25W, 1/4W Through Hole Resistor Axial - Metal Film")
      (fields (field (name "MF") "Yageo") (field (name "MP") "MFR-25FBF52-1K"))
      (libsource (lib "MFR-25FBF52-1K") (part "MFR-25FBF52-1K"))
    )
    (comp (ref "R34")
      (value "1.5K")
      (footprint "RESAD1100W55L680D260")
      (description "1.78 kOhms Â±1% 0.25W, 1/4W Through Hole Resistor Axial - Metal Film")
      (fields (field (name "MF") "Yageo") (field (name "MP") "MFR-25FBF52-1K"))
      (libsource (lib "MFR-25FBF52-1K") (part "MFR-25FBF52-1K"))
    )
    (comp (ref "R35")
      (value "2.2K")
      (footprint "RESAD1100W55L680D260")
      (description "1.78 kOhms Â±1% 0.25W, 1/4W Through Hole Resistor Axial - Metal Film")
      (fields (field (name "MF") "Yageo") (field (name "MP") "MFR-25FBF52-1K"))
      (libsource (lib "MFR-25FBF52-1K") (part "MFR-25FBF52-1K"))
    )
    (comp (ref "R37")
      (value "1K")
      (footprint "RESAD1100W55L680D260")
      (description "1.78 kOhms Â±1% 0.25W, 1/4W Through Hole Resistor Axial - Metal Film")
      (fields (field (name "MF") "Yageo") (field (name "MP") "MFR-25FBF52-1K"))
      (libsource (lib "MFR-25FBF52-1K") (part "MFR-25FBF52-1K"))
    )
    (comp (ref "R38")
      (value "1K")
      (footprint "RESAD1100W55L680D260")
      (description "1.78 kOhms Â±1% 0.25W, 1/4W Through Hole Resistor Axial - Metal Film")
      (fields (field (name "MF") "Yageo") (field (name "MP") "MFR-25FBF52-1K"))
      (libsource (lib "MFR-25FBF52-1K") (part "MFR-25FBF52-1K"))
    )
    (comp (ref "R40")
      (value "1K")
      (footprint "RESAD1100W55L680D260")
      (description "1.78 kOhms Â±1% 0.25W, 1/4W Through Hole Resistor Axial - Metal Film")
      (fields (field (name "MF") "Yageo") (field (name "MP") "MFR-25FBF52-1K"))
      (libsource (lib "MFR-25FBF52-1K") (part "MFR-25FBF52-1K"))
    )
    (comp (ref "R41")
      (value "1K")
      (footprint "RESAD1100W55L680D260")
      (description "1.78 kOhms Â±1% 0.25W, 1/4W Through Hole Resistor Axial - Metal Film")
      (fields (field (name "MF") "Yageo") (field (name "MP") "MFR-25FBF52-1K"))
      (libsource (lib "MFR-25FBF52-1K") (part "MFR-25FBF52-1K"))
    )
    (comp (ref "R43")
      (value "1K")
      (footprint "RESAD1100W55L680D260")
      (description "1.78 kOhms Â±1% 0.25W, 1/4W Through Hole Resistor Axial - Metal Film")
      (fields (field (name "MF") "Yageo") (field (name "MP") "MFR-25FBF52-1K"))
      (libsource (lib "MFR-25FBF52-1K") (part "MFR-25FBF52-1K"))
    )
    (comp (ref "R44")
      (value "1K")
      (footprint "RESAD1100W55L680D260")
      (description "1.78 kOhms Â±1% 0.25W, 1/4W Through Hole Resistor Axial - Metal Film")
      (fields (field (name "MF") "Yageo") (field (name "MP") "MFR-25FBF52-1K"))
      (libsource (lib "MFR-25FBF52-1K") (part "MFR-25FBF52-1K"))
    )
    (comp (ref "R46")
      (value "1K")
      (footprint "RESAD1100W55L680D260")
      (description "1.78 kOhms Â±1% 0.25W, 1/4W Through Hole Resistor Axial - Metal Film")
      (fields (field (name "MF") "Yageo") (field (name "MP") "MFR-25FBF52-1K"))
      (libsource (lib "MFR-25FBF52-1K") (part "MFR-25FBF52-1K"))
    )
    (comp (ref "R47")
      (value "1K")
      (footprint "RESAD1100W55L680D260")
      (description "1.78 kOhms Â±1% 0.25W, 1/4W Through Hole Resistor Axial - Metal Film")
      (fields (field (name "MF") "Yageo") (field (name "MP") "MFR-25FBF52-1K"))
      (libsource (lib "MFR-25FBF52-1K") (part "MFR-25FBF52-1K"))
    )
    (comp (ref "R49")
      (value "1K")
      (footprint "RESAD1100W55L680D260")
      (description "1.78 kOhms Â±1% 0.25W, 1/4W Through Hole Resistor Axial - Metal Film")
      (fields (field (name "MF") "Yageo") (field (name "MP") "MFR-25FBF52-1K"))
      (libsource (lib "MFR-25FBF52-1K") (part "MFR-25FBF52-1K"))
    )
    (comp (ref "R50")
      (value "1K")
      (footprint "RESAD1100W55L680D260")
      (description "1.78 kOhms Â±1% 0.25W, 1/4W Through Hole Resistor Axial - Metal Film")
      (fields (field (name "MF") "Yageo") (field (name "MP") "MFR-25FBF52-1K"))
      (libsource (lib "MFR-25FBF52-1K") (part "MFR-25FBF52-1K"))
    )
    (comp (ref "R51")
      (value "1K")
      (footprint "RESAD1100W55L680D260")
      (description "1.78 kOhms Â±1% 0.25W, 1/4W Through Hole Resistor Axial - Metal Film")
      (fields (field (name "MF") "Yageo") (field (name "MP") "MFR-25FBF52-1K"))
      (libsource (lib "MFR-25FBF52-1K") (part "MFR-25FBF52-1K"))
    )
    (comp (ref "U1")
      (value "LM4562NA")
      (footprint "DIP794W45P254L959H508Q8")
      (description "LM4562 2 - Dual Channels per IC Audio Amplifier Evaluation Board")
      (fields (field (name "MF") "Texas Instruments"))
      (libsource (lib "LM4562NA") (part "LM4562NA"))
    )
    (comp (ref "U2")
      (value "LM4562NA")
      (footprint "DIP794W45P254L959H508Q8")
      (description "LM4562 2 - Dual Channels per IC Audio Amplifier Evaluation Board")
      (fields (field (name "MF") "Texas Instruments"))
      (libsource (lib "LM4562NA") (part "LM4562NA"))
    )
    (comp (ref "U3")
      (value "LM4562NA")
      (footprint "DIP794W45P254L959H508Q8")
      (description "LM4562 2 - Dual Channels per IC Audio Amplifier Evaluation Board")
      (fields (field (name "MF") "Texas Instruments"))
      (libsource (lib "LM4562NA") (part "LM4562NA"))
    )
    (comp (ref "U4")
      (value "LM4562NA")
      (footprint "DIP794W45P254L959H508Q8")
      (description "LM4562 2 - Dual Channels per IC Audio Amplifier Evaluation Board")
      (fields (field (name "MF") "Texas Instruments"))
      (libsource (lib "LM4562NA") (part "LM4562NA"))
    )
    (comp (ref "U5")
      (value "LM4562NA")
      (footprint "DIP794W45P254L959H508Q8")
      (description "LM4562 2 - Dual Channels per IC Audio Amplifier Evaluation Board")
      (fields (field (name "MF") "Texas Instruments"))
      (libsource (lib "LM4562NA") (part "LM4562NA"))
    )
    (comp (ref "U6")
      (value "LM4562NA")
      (footprint "DIP794W45P254L959H508Q8")
      (description "LM4562 2 - Dual Channels per IC Audio Amplifier Evaluation Board")
      (fields (field (name "MF") "Texas Instruments"))
      (libsource (lib "LM4562NA") (part "LM4562NA"))
    )
    (comp (ref "U7")
      (value "LM4562NA")
      (footprint "DIP794W45P254L959H508Q8")
      (description "LM4562 2 - Dual Channels per IC Audio Amplifier Evaluation Board")
      (fields (field (name "MF") "Texas Instruments"))
      (libsource (lib "LM4562NA") (part "LM4562NA"))
    )
    (comp (ref "U8")
      (value "LM4562NA")
      (footprint "DIP794W45P254L959H508Q8")
      (description "LM4562 2 - Dual Channels per IC Audio Amplifier Evaluation Board")
      (fields (field (name "MF") "Texas Instruments"))
      (libsource (lib "LM4562NA") (part "LM4562NA"))
    )
    (comp (ref "U9")
      (value "LM4562NA")
      (footprint "DIP794W45P254L959H508Q8")
      (description "LM4562 2 - Dual Channels per IC Audio Amplifier Evaluation Board")
      (fields (field (name "MF") "Texas Instruments"))
      (libsource (lib "LM4562NA") (part "LM4562NA"))
    )
  )
  (nets
    (net (code "1") (name "+VCC") (class "Default")
      (node (ref "J1") (pin "01") (pinfunction "01_01") (pintype "passive"))
      (node (ref "U1") (pin "8") (pinfunction "V+_8") (pintype "power_in"))
      (node (ref "U2") (pin "8") (pinfunction "V+_8") (pintype "power_in"))
      (node (ref "U3") (pin "8") (pinfunction "V+_8") (pintype "power_in"))
      (node (ref "U4") (pin "8") (pinfunction "V+_8") (pintype "power_in"))
      (node (ref "U5") (pin "8") (pinfunction "V+_8") (pintype "power_in"))
      (node (ref "U6") (pin "8") (pinfunction "V+_8") (pintype "power_in"))
      (node (ref "U7") (pin "8") (pinfunction "V+_8") (pintype "power_in"))
      (node (ref "U8") (pin "8") (pinfunction "V+_8") (pintype "power_in"))
      (node (ref "U9") (pin "8") (pinfunction "V+_8") (pintype "power_in"))
    )
    (net (code "2") (name "-VCC") (class "Default")
      (node (ref "J2") (pin "01") (pinfunction "01_01") (pintype "passive"))
      (node (ref "U1") (pin "4") (pinfunction "V-_4") (pintype "power_in"))
      (node (ref "U2") (pin "4") (pinfunction "V-_4") (pintype "power_in"))
      (node (ref "U3") (pin "4") (pinfunction "V-_4") (pintype "power_in"))
      (node (ref "U4") (pin "4") (pinfunction "V-_4") (pintype "power_in"))
      (node (ref "U5") (pin "4") (pinfunction "V-_4") (pintype "power_in"))
      (node (ref "U6") (pin "4") (pinfunction "V-_4") (pintype "power_in"))
      (node (ref "U7") (pin "4") (pinfunction "V-_4") (pintype "power_in"))
      (node (ref "U8") (pin "4") (pinfunction "V-_4") (pintype "power_in"))
      (node (ref "U9") (pin "4") (pinfunction "V-_4") (pintype "power_in"))
    )
    (net (code "3") (name "GND") (class "Default")
      (node (ref "J3") (pin "01") (pinfunction "01_01") (pintype "passive"))
      (node (ref "R13") (pin "1") (pinfunction "1_1") (pintype "passive"))
      (node (ref "R14") (pin "1") (pinfunction "1_1") (pintype "passive"))
      (node (ref "R20") (pin "1") (pinfunction "1_1") (pintype "passive"))
      (node (ref "R21") (pin "1") (pinfunction "1_1") (pintype "passive"))
      (node (ref "R27") (pin "1") (pinfunction "1_1") (pintype "passive"))
      (node (ref "R28") (pin "1") (pinfunction "1_1") (pintype "passive"))
      (node (ref "R34") (pin "1") (pinfunction "1_1") (pintype "passive"))
      (node (ref "R35") (pin "1") (pinfunction "1_1") (pintype "passive"))
      (node (ref "R6") (pin "1") (pinfunction "1_1") (pintype "passive"))
      (node (ref "R7") (pin "1") (pinfunction "1_1") (pintype "passive"))
      (node (ref "U1") (pin "5") (pinfunction "INB+_5") (pintype "input"))
      (node (ref "U2") (pin "3") (pinfunction "INA+_3") (pintype "input"))
      (node (ref "U2") (pin "5") (pinfunction "INB+_5") (pintype "input"))
      (node (ref "U3") (pin "3") (pinfunction "INA+_3") (pintype "input"))
      (node (ref "U3") (pin "5") (pinfunction "INB+_5") (pintype "input"))
      (node (ref "U4") (pin "3") (pinfunction "INA+_3") (pintype "input"))
      (node (ref "U4") (pin "5") (pinfunction "INB+_5") (pintype "input"))
      (node (ref "U5") (pin "3") (pinfunction "INA+_3") (pintype "input"))
      (node (ref "U5") (pin "5") (pinfunction "INB+_5") (pintype "input"))
      (node (ref "U6") (pin "3") (pinfunction "INA+_3") (pintype "input"))
      (node (ref "U6") (pin "5") (pinfunction "INB+_5") (pintype "input"))
      (node (ref "U7") (pin "3") (pinfunction "INA+_3") (pintype "input"))
      (node (ref "U8") (pin "3") (pinfunction "INA+_3") (pintype "input"))
      (node (ref "U8") (pin "5") (pinfunction "INB+_5") (pintype "input"))
      (node (ref "U9") (pin "3") (pinfunction "INA+_3") (pintype "input"))
      (node (ref "U9") (pin "5") (pinfunction "INB+_5") (pintype "input"))
    )
    (net (code "4") (name "Net-(B1-CW)") (class "Default")
      (node (ref "B1") (pin "3") (pinfunction "CW_3") (pintype "passive"))
      (node (ref "R37") (pin "1") (pinfunction "1_1") (pintype "passive"))
      (node (ref "U7") (pin "2") (pinfunction "INA-_2") (pintype "input"))
    )
    (net (code "5") (name "Net-(B1-S)") (class "Default")
      (node (ref "B1") (pin "2") (pinfunction "S_2") (pintype "passive"))
      (node (ref "C31") (pin "P") (pinfunction "P_P") (pintype "passive"))
      (node (ref "J5") (pin "01") (pinfunction "01_01") (pintype "passive"))
      (node (ref "U7") (pin "1") (pinfunction "OUTA_1") (pintype "output"))
    )
    (net (code "6") (name "Net-(B2-CW)") (class "Default")
      (node (ref "B2") (pin "3") (pinfunction "CW_3") (pintype "passive"))
      (node (ref "R40") (pin "1") (pinfunction "1_1") (pintype "passive"))
      (node (ref "U8") (pin "6") (pinfunction "INB-_6") (pintype "input"))
    )
    (net (code "7") (name "Net-(B2-S)") (class "Default")
      (node (ref "B2") (pin "2") (pinfunction "S_2") (pintype "passive"))
      (node (ref "C32") (pin "P") (pinfunction "P_P") (pintype "passive"))
      (node (ref "J6") (pin "01") (pinfunction "01_01") (pintype "passive"))
      (node (ref "U8") (pin "7") (pinfunction "OUTB_7") (pintype "output"))
    )
    (net (code "8") (name "Net-(B3-CW)") (class "Default")
      (node (ref "B3") (pin "3") (pinfunction "CW_3") (pintype "passive"))
      (node (ref "R43") (pin "1") (pinfunction "1_1") (pintype "passive"))
      (node (ref "U8") (pin "2") (pinfunction "INA-_2") (pintype "input"))
    )
    (net (code "9") (name "Net-(B3-S)") (class "Default")
      (node (ref "B3") (pin "2") (pinfunction "S_2") (pintype "passive"))
      (node (ref "C33") (pin "P") (pinfunction "P_P") (pintype "passive"))
      (node (ref "J7") (pin "01") (pinfunction "01_01") (pintype "passive"))
      (node (ref "U8") (pin "1") (pinfunction "OUTA_1") (pintype "output"))
    )
    (net (code "10") (name "Net-(B4-CW)") (class "Default")
      (node (ref "B4") (pin "3") (pinfunction "CW_3") (pintype "passive"))
      (node (ref "R46") (pin "1") (pinfunction "1_1") (pintype "passive"))
      (node (ref "U9") (pin "6") (pinfunction "INB-_6") (pintype "input"))
    )
    (net (code "11") (name "Net-(B4-S)") (class "Default")
      (node (ref "B4") (pin "2") (pinfunction "S_2") (pintype "passive"))
      (node (ref "C34") (pin "P") (pinfunction "P_P") (pintype "passive"))
      (node (ref "J9") (pin "01") (pinfunction "01_01") (pintype "passive"))
      (node (ref "U9") (pin "7") (pinfunction "OUTB_7") (pintype "output"))
    )
    (net (code "12") (name "Net-(B5-CW)") (class "Default")
      (node (ref "B5") (pin "3") (pinfunction "CW_3") (pintype "passive"))
      (node (ref "R49") (pin "1") (pinfunction "1_1") (pintype "passive"))
      (node (ref "U9") (pin "2") (pinfunction "INA-_2") (pintype "input"))
    )
    (net (code "13") (name "Net-(B5-S)") (class "Default")
      (node (ref "B5") (pin "2") (pinfunction "S_2") (pintype "passive"))
      (node (ref "C35") (pin "P") (pinfunction "P_P") (pintype "passive"))
      (node (ref "J10") (pin "01") (pinfunction "01_01") (pintype "passive"))
      (node (ref "U9") (pin "1") (pinfunction "OUTA_1") (pintype "output"))
    )
    (net (code "14") (name "Net-(C1-Pad1)") (class "Default")
      (node (ref "C1") (pin "1") (pinfunction "1_1") (pintype "passive"))
      (node (ref "C4") (pin "1") (pinfunction "1_1") (pintype "passive"))
      (node (ref "R4") (pin "2") (pinfunction "2_2") (pintype "passive"))
      (node (ref "R6") (pin "2") (pinfunction "2_2") (pintype "passive"))
    )
    (net (code "15") (name "Net-(C2-Pad1)") (class "Default")
      (node (ref "C2") (pin "1") (pinfunction "1_1") (pintype "passive"))
      (node (ref "C5") (pin "1") (pinfunction "1_1") (pintype "passive"))
      (node (ref "R5") (pin "1") (pinfunction "1_1") (pintype "passive"))
      (node (ref "R7") (pin "2") (pinfunction "2_2") (pintype "passive"))
    )
    (net (code "16") (name "Net-(C3-PadN)") (class "Default")
      (node (ref "C3") (pin "N") (pinfunction "N_N") (pintype "passive"))
      (node (ref "R4") (pin "1") (pinfunction "1_1") (pintype "passive"))
    )
    (net (code "17") (name "Net-(C3-PadP)") (class "Default")
      (node (ref "C3") (pin "P") (pinfunction "P_P") (pintype "passive"))
      (node (ref "R3") (pin "2") (pinfunction "2_2") (pintype "passive"))
    )
    (net (code "18") (name "Net-(C6-PadN)") (class "Default")
      (node (ref "C6") (pin "N") (pinfunction "N_N") (pintype "passive"))
      (node (ref "R37") (pin "2") (pinfunction "2_2") (pintype "passive"))
    )
    (net (code "19") (name "Net-(C9-PadN)") (class "Default")
      (node (ref "C9") (pin "N") (pinfunction "N_N") (pintype "passive"))
      (node (ref "R11") (pin "1") (pinfunction "1_1") (pintype "passive"))
    )
    (net (code "20") (name "Net-(C9-PadP)") (class "Default")
      (node (ref "C9") (pin "P") (pinfunction "P_P") (pintype "passive"))
      (node (ref "R10") (pin "2") (pinfunction "2_2") (pintype "passive"))
    )
    (net (code "21") (name "Net-(C10-Pad1)") (class "Default")
      (node (ref "C10") (pin "1") (pinfunction "1_1") (pintype "passive"))
      (node (ref "C7") (pin "1") (pinfunction "1_1") (pintype "passive"))
      (node (ref "R11") (pin "2") (pinfunction "2_2") (pintype "passive"))
      (node (ref "R13") (pin "2") (pinfunction "2_2") (pintype "passive"))
    )
    (net (code "22") (name "Net-(C11-Pad1)") (class "Default")
      (node (ref "C11") (pin "1") (pinfunction "1_1") (pintype "passive"))
      (node (ref "C8") (pin "1") (pinfunction "1_1") (pintype "passive"))
      (node (ref "R12") (pin "1") (pinfunction "1_1") (pintype "passive"))
      (node (ref "R14") (pin "2") (pinfunction "2_2") (pintype "passive"))
    )
    (net (code "23") (name "Net-(C12-PadN)") (class "Default")
      (node (ref "C12") (pin "N") (pinfunction "N_N") (pintype "passive"))
      (node (ref "R40") (pin "2") (pinfunction "2_2") (pintype "passive"))
    )
    (net (code "24") (name "Net-(C13-Pad1)") (class "Default")
      (node (ref "C13") (pin "1") (pinfunction "1_1") (pintype "passive"))
      (node (ref "C16") (pin "1") (pinfunction "1_1") (pintype "passive"))
      (node (ref "R18") (pin "2") (pinfunction "2_2") (pintype "passive"))
      (node (ref "R20") (pin "2") (pinfunction "2_2") (pintype "passive"))
    )
    (net (code "25") (name "Net-(C14-Pad1)") (class "Default")
      (node (ref "C14") (pin "1") (pinfunction "1_1") (pintype "passive"))
      (node (ref "C17") (pin "1") (pinfunction "1_1") (pintype "passive"))
      (node (ref "R19") (pin "1") (pinfunction "1_1") (pintype "passive"))
      (node (ref "R21") (pin "2") (pinfunction "2_2") (pintype "passive"))
    )
    (net (code "26") (name "Net-(C15-PadN)") (class "Default")
      (node (ref "C15") (pin "N") (pinfunction "N_N") (pintype "passive"))
      (node (ref "R18") (pin "1") (pinfunction "1_1") (pintype "passive"))
    )
    (net (code "27") (name "Net-(C15-PadP)") (class "Default")
      (node (ref "C15") (pin "P") (pinfunction "P_P") (pintype "passive"))
      (node (ref "R17") (pin "2") (pinfunction "2_2") (pintype "passive"))
    )
    (net (code "28") (name "Net-(C18-PadN)") (class "Default")
      (node (ref "C18") (pin "N") (pinfunction "N_N") (pintype "passive"))
      (node (ref "R43") (pin "2") (pinfunction "2_2") (pintype "passive"))
    )
    (net (code "29") (name "Net-(C19-Pad1)") (class "Default")
      (node (ref "C19") (pin "1") (pinfunction "1_1") (pintype "passive"))
      (node (ref "C22") (pin "1") (pinfunction "1_1") (pintype "passive"))
      (node (ref "R25") (pin "2") (pinfunction "2_2") (pintype "passive"))
      (node (ref "R27") (pin "2") (pinfunction "2_2") (pintype "passive"))
    )
    (net (code "30") (name "Net-(C20-Pad1)") (class "Default")
      (node (ref "C20") (pin "1") (pinfunction "1_1") (pintype "passive"))
      (node (ref "C23") (pin "1") (pinfunction "1_1") (pintype "passive"))
      (node (ref "R26") (pin "1") (pinfunction "1_1") (pintype "passive"))
      (node (ref "R28") (pin "2") (pinfunction "2_2") (pintype "passive"))
    )
    (net (code "31") (name "Net-(C21-PadN)") (class "Default")
      (node (ref "C21") (pin "N") (pinfunction "N_N") (pintype "passive"))
      (node (ref "R25") (pin "1") (pinfunction "1_1") (pintype "passive"))
    )
    (net (code "32") (name "Net-(C21-PadP)") (class "Default")
      (node (ref "C21") (pin "P") (pinfunction "P_P") (pintype "passive"))
      (node (ref "R24") (pin "2") (pinfunction "2_2") (pintype "passive"))
    )
    (net (code "33") (name "Net-(C24-PadN)") (class "Default")
      (node (ref "C24") (pin "N") (pinfunction "N_N") (pintype "passive"))
      (node (ref "R46") (pin "2") (pinfunction "2_2") (pintype "passive"))
    )
    (net (code "34") (name "Net-(C25-Pad1)") (class "Default")
      (node (ref "C25") (pin "1") (pinfunction "1_1") (pintype "passive"))
      (node (ref "C28") (pin "1") (pinfunction "1_1") (pintype "passive"))
      (node (ref "R32") (pin "2") (pinfunction "2_2") (pintype "passive"))
      (node (ref "R34") (pin "2") (pinfunction "2_2") (pintype "passive"))
    )
    (net (code "35") (name "Net-(C26-Pad1)") (class "Default")
      (node (ref "C26") (pin "1") (pinfunction "1_1") (pintype "passive"))
      (node (ref "C29") (pin "1") (pinfunction "1_1") (pintype "passive"))
      (node (ref "R33") (pin "1") (pinfunction "1_1") (pintype "passive"))
      (node (ref "R35") (pin "2") (pinfunction "2_2") (pintype "passive"))
    )
    (net (code "36") (name "Net-(C27-PadN)") (class "Default")
      (node (ref "C27") (pin "N") (pinfunction "N_N") (pintype "passive"))
      (node (ref "R32") (pin "1") (pinfunction "1_1") (pintype "passive"))
    )
    (net (code "37") (name "Net-(C27-PadP)") (class "Default")
      (node (ref "C27") (pin "P") (pinfunction "P_P") (pintype "passive"))
      (node (ref "R31") (pin "2") (pinfunction "2_2") (pintype "passive"))
    )
    (net (code "38") (name "Net-(C30-PadN)") (class "Default")
      (node (ref "C30") (pin "N") (pinfunction "N_N") (pintype "passive"))
      (node (ref "R49") (pin "2") (pinfunction "2_2") (pintype "passive"))
    )
    (net (code "39") (name "Net-(C31-PadN)") (class "Default")
      (node (ref "C31") (pin "N") (pinfunction "N_N") (pintype "passive"))
      (node (ref "R38") (pin "2") (pinfunction "2_2") (pintype "passive"))
    )
    (net (code "40") (name "Net-(C32-PadN)") (class "Default")
      (node (ref "C32") (pin "N") (pinfunction "N_N") (pintype "passive"))
      (node (ref "R41") (pin "2") (pinfunction "2_2") (pintype "passive"))
    )
    (net (code "41") (name "Net-(C33-PadN)") (class "Default")
      (node (ref "C33") (pin "N") (pinfunction "N_N") (pintype "passive"))
      (node (ref "R44") (pin "2") (pinfunction "2_2") (pintype "passive"))
    )
    (net (code "42") (name "Net-(C34-PadN)") (class "Default")
      (node (ref "C34") (pin "N") (pinfunction "N_N") (pintype "passive"))
      (node (ref "R47") (pin "2") (pinfunction "2_2") (pintype "passive"))
    )
    (net (code "43") (name "Net-(C35-PadN)") (class "Default")
      (node (ref "C35") (pin "N") (pinfunction "N_N") (pintype "passive"))
      (node (ref "R50") (pin "2") (pinfunction "2_2") (pintype "passive"))
    )
    (net (code "44") (name "Net-(U1A-INA+)") (class "Default")
      (node (ref "J4") (pin "01") (pinfunction "01_01") (pintype "passive"))
      (node (ref "U1") (pin "3") (pinfunction "INA+_3") (pintype "input"))
    )
    (net (code "45") (name "Net-(U1A-INA-)") (class "Default")
      (node (ref "R10") (pin "1") (pinfunction "1_1") (pintype "passive"))
      (node (ref "R17") (pin "1") (pinfunction "1_1") (pintype "passive"))
      (node (ref "R24") (pin "1") (pinfunction "1_1") (pintype "passive"))
      (node (ref "R3") (pin "1") (pinfunction "1_1") (pintype "passive"))
      (node (ref "R31") (pin "1") (pinfunction "1_1") (pintype "passive"))
      (node (ref "U1") (pin "1") (pinfunction "OUTA_1") (pintype "output"))
      (node (ref "U1") (pin "2") (pinfunction "INA-_2") (pintype "input"))
    )
    (net (code "46") (name "Net-(U1B-INB-)") (class "Default")
      (node (ref "R38") (pin "1") (pinfunction "1_1") (pintype "passive"))
      (node (ref "R41") (pin "1") (pinfunction "1_1") (pintype "passive"))
      (node (ref "R44") (pin "1") (pinfunction "1_1") (pintype "passive"))
      (node (ref "R47") (pin "1") (pinfunction "1_1") (pintype "passive"))
      (node (ref "R50") (pin "1") (pinfunction "1_1") (pintype "passive"))
      (node (ref "R51") (pin "2") (pinfunction "2_2") (pintype "passive"))
      (node (ref "U1") (pin "6") (pinfunction "INB-_6") (pintype "input"))
    )
    (net (code "47") (name "Net-(U1B-OUTB)") (class "Default")
      (node (ref "J8") (pin "01") (pinfunction "01_01") (pintype "passive"))
      (node (ref "R51") (pin "1") (pinfunction "1_1") (pintype "passive"))
      (node (ref "U1") (pin "7") (pinfunction "OUTB_7") (pintype "output"))
    )
    (net (code "48") (name "Net-(U2A-INA-)") (class "Default")
      (node (ref "C4") (pin "2") (pinfunction "2_2") (pintype "passive"))
      (node (ref "R1") (pin "1") (pinfunction "1_1") (pintype "passive"))
      (node (ref "U2") (pin "2") (pinfunction "INA-_2") (pintype "input"))
    )
    (net (code "49") (name "Net-(U2A-OUTA)") (class "Default")
      (node (ref "C1") (pin "2") (pinfunction "2_2") (pintype "passive"))
      (node (ref "R1") (pin "2") (pinfunction "2_2") (pintype "passive"))
      (node (ref "R5") (pin "2") (pinfunction "2_2") (pintype "passive"))
      (node (ref "U2") (pin "1") (pinfunction "OUTA_1") (pintype "output"))
    )
    (net (code "50") (name "Net-(U2B-INB-)") (class "Default")
      (node (ref "C5") (pin "2") (pinfunction "2_2") (pintype "passive"))
      (node (ref "R2") (pin "1") (pinfunction "1_1") (pintype "passive"))
      (node (ref "U2") (pin "6") (pinfunction "INB-_6") (pintype "input"))
    )
    (net (code "51") (name "Net-(U2B-OUTB)") (class "Default")
      (node (ref "C2") (pin "2") (pinfunction "2_2") (pintype "passive"))
      (node (ref "C6") (pin "P") (pinfunction "P_P") (pintype "passive"))
      (node (ref "R2") (pin "2") (pinfunction "2_2") (pintype "passive"))
      (node (ref "U2") (pin "7") (pinfunction "OUTB_7") (pintype "output"))
    )
    (net (code "52") (name "Net-(U3A-INA-)") (class "Default")
      (node (ref "C10") (pin "2") (pinfunction "2_2") (pintype "passive"))
      (node (ref "R8") (pin "1") (pinfunction "1_1") (pintype "passive"))
      (node (ref "U3") (pin "2") (pinfunction "INA-_2") (pintype "input"))
    )
    (net (code "53") (name "Net-(U3A-OUTA)") (class "Default")
      (node (ref "C7") (pin "2") (pinfunction "2_2") (pintype "passive"))
      (node (ref "R12") (pin "2") (pinfunction "2_2") (pintype "passive"))
      (node (ref "R8") (pin "2") (pinfunction "2_2") (pintype "passive"))
      (node (ref "U3") (pin "1") (pinfunction "OUTA_1") (pintype "output"))
    )
    (net (code "54") (name "Net-(U3B-INB-)") (class "Default")
      (node (ref "C11") (pin "2") (pinfunction "2_2") (pintype "passive"))
      (node (ref "R9") (pin "1") (pinfunction "1_1") (pintype "passive"))
      (node (ref "U3") (pin "6") (pinfunction "INB-_6") (pintype "input"))
    )
    (net (code "55") (name "Net-(U3B-OUTB)") (class "Default")
      (node (ref "C12") (pin "P") (pinfunction "P_P") (pintype "passive"))
      (node (ref "C8") (pin "2") (pinfunction "2_2") (pintype "passive"))
      (node (ref "R9") (pin "2") (pinfunction "2_2") (pintype "passive"))
      (node (ref "U3") (pin "7") (pinfunction "OUTB_7") (pintype "output"))
    )
    (net (code "56") (name "Net-(U4A-INA-)") (class "Default")
      (node (ref "C16") (pin "2") (pinfunction "2_2") (pintype "passive"))
      (node (ref "R15") (pin "1") (pinfunction "1_1") (pintype "passive"))
      (node (ref "U4") (pin "2") (pinfunction "INA-_2") (pintype "input"))
    )
    (net (code "57") (name "Net-(U4A-OUTA)") (class "Default")
      (node (ref "C13") (pin "2") (pinfunction "2_2") (pintype "passive"))
      (node (ref "R15") (pin "2") (pinfunction "2_2") (pintype "passive"))
      (node (ref "R19") (pin "2") (pinfunction "2_2") (pintype "passive"))
      (node (ref "U4") (pin "1") (pinfunction "OUTA_1") (pintype "output"))
    )
    (net (code "58") (name "Net-(U4B-INB-)") (class "Default")
      (node (ref "C17") (pin "2") (pinfunction "2_2") (pintype "passive"))
      (node (ref "R16") (pin "1") (pinfunction "1_1") (pintype "passive"))
      (node (ref "U4") (pin "6") (pinfunction "INB-_6") (pintype "input"))
    )
    (net (code "59") (name "Net-(U4B-OUTB)") (class "Default")
      (node (ref "C14") (pin "2") (pinfunction "2_2") (pintype "passive"))
      (node (ref "C18") (pin "P") (pinfunction "P_P") (pintype "passive"))
      (node (ref "R16") (pin "2") (pinfunction "2_2") (pintype "passive"))
      (node (ref "U4") (pin "7") (pinfunction "OUTB_7") (pintype "output"))
    )
    (net (code "60") (name "Net-(U5A-INA-)") (class "Default")
      (node (ref "C22") (pin "2") (pinfunction "2_2") (pintype "passive"))
      (node (ref "R22") (pin "1") (pinfunction "1_1") (pintype "passive"))
      (node (ref "U5") (pin "2") (pinfunction "INA-_2") (pintype "input"))
    )
    (net (code "61") (name "Net-(U5A-OUTA)") (class "Default")
      (node (ref "C19") (pin "2") (pinfunction "2_2") (pintype "passive"))
      (node (ref "R22") (pin "2") (pinfunction "2_2") (pintype "passive"))
      (node (ref "R26") (pin "2") (pinfunction "2_2") (pintype "passive"))
      (node (ref "U5") (pin "1") (pinfunction "OUTA_1") (pintype "output"))
    )
    (net (code "62") (name "Net-(U5B-INB-)") (class "Default")
      (node (ref "C23") (pin "2") (pinfunction "2_2") (pintype "passive"))
      (node (ref "R23") (pin "1") (pinfunction "1_1") (pintype "passive"))
      (node (ref "U5") (pin "6") (pinfunction "INB-_6") (pintype "input"))
    )
    (net (code "63") (name "Net-(U5B-OUTB)") (class "Default")
      (node (ref "C20") (pin "2") (pinfunction "2_2") (pintype "passive"))
      (node (ref "C24") (pin "P") (pinfunction "P_P") (pintype "passive"))
      (node (ref "R23") (pin "2") (pinfunction "2_2") (pintype "passive"))
      (node (ref "U5") (pin "7") (pinfunction "OUTB_7") (pintype "output"))
    )
    (net (code "64") (name "Net-(U6A-INA-)") (class "Default")
      (node (ref "C28") (pin "2") (pinfunction "2_2") (pintype "passive"))
      (node (ref "R29") (pin "1") (pinfunction "1_1") (pintype "passive"))
      (node (ref "U6") (pin "2") (pinfunction "INA-_2") (pintype "input"))
    )
    (net (code "65") (name "Net-(U6A-OUTA)") (class "Default")
      (node (ref "C25") (pin "2") (pinfunction "2_2") (pintype "passive"))
      (node (ref "R29") (pin "2") (pinfunction "2_2") (pintype "passive"))
      (node (ref "R33") (pin "2") (pinfunction "2_2") (pintype "passive"))
      (node (ref "U6") (pin "1") (pinfunction "OUTA_1") (pintype "output"))
    )
    (net (code "66") (name "Net-(U6B-INB-)") (class "Default")
      (node (ref "C29") (pin "2") (pinfunction "2_2") (pintype "passive"))
      (node (ref "R30") (pin "1") (pinfunction "1_1") (pintype "passive"))
      (node (ref "U6") (pin "6") (pinfunction "INB-_6") (pintype "input"))
    )
    (net (code "67") (name "Net-(U6B-OUTB)") (class "Default")
      (node (ref "C26") (pin "2") (pinfunction "2_2") (pintype "passive"))
      (node (ref "C30") (pin "P") (pinfunction "P_P") (pintype "passive"))
      (node (ref "R30") (pin "2") (pinfunction "2_2") (pintype "passive"))
      (node (ref "U6") (pin "7") (pinfunction "OUTB_7") (pintype "output"))
    )
    (net (code "68") (name "unconnected-(B1-CCW-Pad1)") (class "Default")
      (node (ref "B1") (pin "1") (pinfunction "CCW_1") (pintype "passive+no_connect"))
    )
    (net (code "69") (name "unconnected-(B2-CCW-Pad1)") (class "Default")
      (node (ref "B2") (pin "1") (pinfunction "CCW_1") (pintype "passive+no_connect"))
    )
    (net (code "70") (name "unconnected-(B3-CCW-Pad1)") (class "Default")
      (node (ref "B3") (pin "1") (pinfunction "CCW_1") (pintype "passive+no_connect"))
    )
    (net (code "71") (name "unconnected-(B4-CCW-Pad1)") (class "Default")
      (node (ref "B4") (pin "1") (pinfunction "CCW_1") (pintype "passive+no_connect"))
    )
    (net (code "72") (name "unconnected-(B5-CCW-Pad1)") (class "Default")
      (node (ref "B5") (pin "1") (pinfunction "CCW_1") (pintype "passive+no_connect"))
    )
    (net (code "73") (name "unconnected-(U7B-INB+-Pad5)") (class "Default")
      (node (ref "U7") (pin "5") (pinfunction "INB+_5") (pintype "input+no_connect"))
    )
    (net (code "74") (name "unconnected-(U7B-INB--Pad6)") (class "Default")
      (node (ref "U7") (pin "6") (pinfunction "INB-_6") (pintype "input+no_connect"))
    )
    (net (code "75") (name "unconnected-(U7B-OUTB-Pad7)") (class "Default")
      (node (ref "U7") (pin "7") (pinfunction "OUTB_7") (pintype "output+no_connect"))
    )
  )
)
